# 10-power.net
KiCad netlist of a schematic drawn in Altium Designer
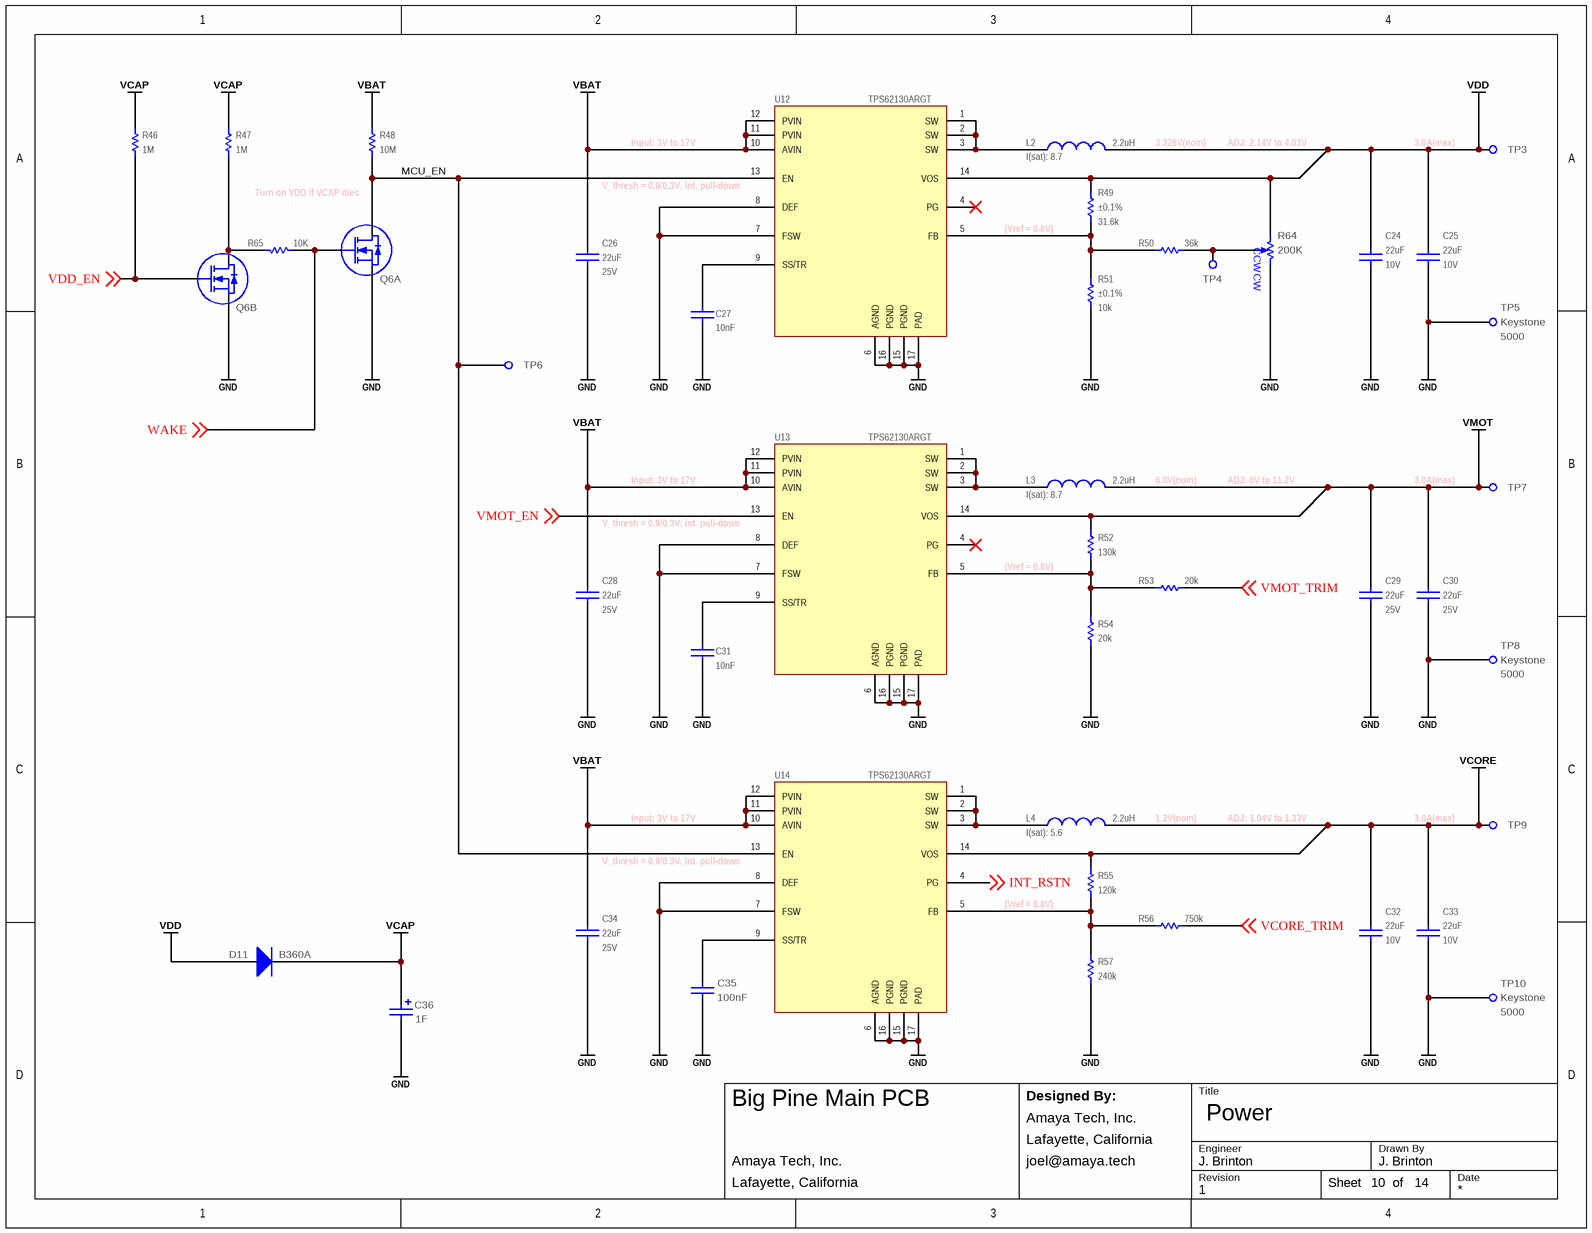
[diagram p0: 10-power.SchDoc]

(export (version "E")
  (design (tool "Eeschema 10.0.6"))
  (components
    (comp (ref "C24")
      (value "22uF")
      (footprint "CAPC200X125X145L45N")
      (description "Ceramic Capacitor 22uF ±20% 10V X7S 0805")
      (fields
        (field (name "MANUFACTURER") "TDK")
        (field (name "TOLERANCE") "±20%")
        (field (name "VOLTAGE") "10V")
      )
      (libsource (lib "") (part "CAP_1"))
    )
    (comp (ref "C25")
      (value "22uF")
      (footprint "CAPC200X125X145L45N")
      (description "Ceramic Capacitor 22uF ±20% 10V X7S 0805")
      (fields
        (field (name "MANUFACTURER") "TDK")
        (field (name "TOLERANCE") "±20%")
        (field (name "VOLTAGE") "10V")
      )
      (libsource (lib "") (part "CAP_1"))
    )
    (comp (ref "C26")
      (value "22uF")
      (footprint "CAPC320X250X270L50N")
      (description "Ceramic Capacitor 22uF ±10% 25V X7R 1210")
      (fields
        (field (name "MANUFACTURER") "Murata")
        (field (name "TOLERANCE") "±10%")
        (field (name "VOLTAGE") "25V")
      )
      (libsource (lib "generic") (part "CAP"))
    )
    (comp (ref "C27")
      (value "10nF")
      (footprint "CAPC100X50X55L25N")
      (description "Ceramic Capacitor 10nF ±10% 50V X7R 0402")
      (fields (field (name "MANUFACTURER") "Murata") (field (name "TOLERANCE") "±10%"))
      (libsource (lib "generic") (part "CAP"))
    )
    (comp (ref "C28")
      (value "22uF")
      (footprint "CAPC320X250X270L50N")
      (description "Ceramic Capacitor 22uF ±10% 25V X7R 1210")
      (fields
        (field (name "MANUFACTURER") "Murata")
        (field (name "TOLERANCE") "±10%")
        (field (name "VOLTAGE") "25V")
      )
      (libsource (lib "generic") (part "CAP"))
    )
    (comp (ref "C29")
      (value "22uF")
      (footprint "CAPC320X250X270L50N")
      (description "Ceramic Capacitor 22uF ±10% 25V X7R 1210")
      (fields
        (field (name "MANUFACTURER") "Murata")
        (field (name "TOLERANCE") "±10%")
        (field (name "VOLTAGE") "25V")
      )
      (libsource (lib "generic") (part "CAP"))
    )
    (comp (ref "C30")
      (value "22uF")
      (footprint "CAPC320X250X270L50N")
      (description "Ceramic Capacitor 22uF ±10% 25V X7R 1210")
      (fields
        (field (name "MANUFACTURER") "Murata")
        (field (name "TOLERANCE") "±10%")
        (field (name "VOLTAGE") "25V")
      )
      (libsource (lib "generic") (part "CAP"))
    )
    (comp (ref "C31")
      (value "10nF")
      (footprint "CAPC100X50X55L25N")
      (description "Ceramic Capacitor 10nF ±10% 50V X7R 0402")
      (fields (field (name "MANUFACTURER") "Murata") (field (name "TOLERANCE") "±10%"))
      (libsource (lib "generic") (part "CAP"))
    )
    (comp (ref "C32")
      (value "22uF")
      (footprint "CAPC200X125X145L45N")
      (description "Ceramic Capacitor 22uF ±20% 10V X7S 0805")
      (fields
        (field (name "MANUFACTURER") "TDK")
        (field (name "TOLERANCE") "±20%")
        (field (name "VOLTAGE") "10V")
      )
      (libsource (lib "") (part "CAP_1"))
    )
    (comp (ref "C33")
      (value "22uF")
      (footprint "CAPC200X125X145L45N")
      (description "Ceramic Capacitor 22uF ±20% 10V X7S 0805")
      (fields
        (field (name "MANUFACTURER") "TDK")
        (field (name "TOLERANCE") "±20%")
        (field (name "VOLTAGE") "10V")
      )
      (libsource (lib "") (part "CAP_1"))
    )
    (comp (ref "C34")
      (value "22uF")
      (footprint "CAPC320X250X270L50N")
      (description "Ceramic Capacitor 22uF ±10% 25V X7R 1210")
      (fields
        (field (name "MANUFACTURER") "Murata")
        (field (name "TOLERANCE") "±10%")
        (field (name "VOLTAGE") "25V")
      )
      (libsource (lib "generic") (part "CAP"))
    )
    (comp (ref "C35")
      (value "100nF")
      (footprint "CAPC200X125X145L45N")
      (description "Ceramic Capacitor 100nF ±10% 50V X7R 0805")
      (fields (field (name "MANUFACTURER") "Murata") (field (name "TOLERANCE") "±10%"))
      (libsource (lib "capacitors") (part "CAP"))
    )
    (comp (ref "C36")
      (value "1F")
      (footprint "DBJ-5R5D105T")
      (description "Super Capacitor 1F 5.5V Leaded")
      (fields (field (name "MANUFACTURER") "Elna") (field (name "VOLTAGE") "5.5V"))
      (libsource (lib "generic") (part "CAP_POL"))
    )
    (comp (ref "D11")
      (value "B360A")
      (footprint "SMA")
      (description "DIODE SCHOTTKY 60V 3A SMA")
      (fields (field (name "MANUFACTURER") "Diodes Inc"))
      (libsource (lib "diodes_inc") (part "D360A"))
    )
    (comp (ref "L2")
      (value "2.2uH")
      (footprint "coilcraft:XAL5030")
      (description "Shielded Power Inductor 2.2uH, 8.7A")
      (fields
        (field (name "MANUFACTURER") "Coilcraft")
        (field (name "I(SAT)") "8.7")
        (field (name "Comment") "XAL5030-332ME")
      )
      (libsource (lib "generic") (part "INDUCTOR"))
    )
    (comp (ref "L3")
      (value "2.2uH")
      (footprint "coilcraft:XAL5030")
      (description "Shielded Power Inductor 2.2uH, 8.7A")
      (fields
        (field (name "MANUFACTURER") "Coilcraft")
        (field (name "I(SAT)") "8.7")
        (field (name "Comment") "XAL5030-332ME")
      )
      (libsource (lib "generic") (part "INDUCTOR"))
    )
    (comp (ref "L4")
      (value "2.2uH")
      (footprint "coilcraft:XFL4020")
      (description "Shielded Power Inductor 2.2uH, 5.6A")
      (fields
        (field (name "MANUFACTURER") "Coilcraft")
        (field (name "I(SAT)") "5.6")
        (field (name "Comment") "XAL4020-222ME_")
      )
      (libsource (lib "generic") (part "INDUCTOR"))
    )
    (comp (ref "Q6")
      (value "2N7002DWQ-7-F")
      (footprint "SOT363")
      (description "Dual N-Channel Enhancement Mode MOSFET")
      (fields (field (name "MANUFACTURER") "Diodes, Inc."))
      (libsource (lib "") (part "2N7002DW-7-F_1"))
    )
    (comp (ref "R46")
      (value "1M")
      (footprint "RESC2012X70N")
      (description "Thick Film Resistor 1M ±1% 0805")
      (fields (field (name "MANUFACTURER") "Panasonic") (field (name "TOLERANCE") "±1%"))
      (libsource (lib "Graviton") (part "RES 0402"))
    )
    (comp (ref "R47")
      (value "1M")
      (footprint "RESC2012X70N")
      (description "Thick Film Resistor 1M ±1% 0805")
      (fields (field (name "MANUFACTURER") "Panasonic") (field (name "TOLERANCE") "±1%"))
      (libsource (lib "Graviton") (part "RES 0402"))
    )
    (comp (ref "R48")
      (value "10M")
      (footprint "RESC2012X70N")
      (description "Thick Film Resistor 10M ±1% 0805")
      (fields (field (name "MANUFACTURER") "Panasonic") (field (name "TOLERANCE") "±5%"))
      (libsource (lib "Graviton") (part "RES 0402"))
    )
    (comp (ref "R49")
      (value "31.6k")
      (footprint "RESC2012X70N")
      (description "Thin Film Resistor 31.6k ±0.1% 0.125W 100V 0805")
      (fields
        (field (name "TOLERANCE") "±0.1%")
        (field (name "MANUFACTURER") "Panasonic")
        (field (name "VOLTAGE") "100")
      )
      (libsource (lib "generic") (part "RES"))
    )
    (comp (ref "R50")
      (value "36k")
      (footprint "RESC2012X70N")
      (description "Thick Film Resistor 36k ±1% 0805")
      (fields (field (name "MANUFACTURER") "Panasonic") (field (name "TOLERANCE") "±1%"))
      (libsource (lib "Graviton") (part "RES 0402"))
    )
    (comp (ref "R51")
      (value "10k")
      (footprint "RESC2012X70N")
      (description "Thin Film Resistor 10k ±0.1% 0.125W 100V 0805")
      (fields
        (field (name "TOLERANCE") "±0.1%")
        (field (name "MANUFACTURER") "Panasonic")
        (field (name "VOLTAGE") "100")
      )
      (libsource (lib "generic") (part "RES"))
    )
    (comp (ref "R52")
      (value "130k")
      (footprint "RESC2012X70N")
      (description "Thick Film Resistor 130k ±1% 0805")
      (fields (field (name "MANUFACTURER") "Panasonic") (field (name "TOLERANCE") "±1%"))
      (libsource (lib "Graviton") (part "RES 0402"))
    )
    (comp (ref "R53")
      (value "20k")
      (footprint "RESC2012X70N")
      (description "Thick Film Resistor 20k ±1% 0805")
      (fields (field (name "MANUFACTURER") "Panasonic") (field (name "TOLERANCE") "±1%"))
      (libsource (lib "Graviton") (part "RES 0402"))
    )
    (comp (ref "R54")
      (value "20k")
      (footprint "RESC2012X70N")
      (description "Thick Film Resistor 20k ±1% 0805")
      (fields (field (name "MANUFACTURER") "Panasonic") (field (name "TOLERANCE") "±1%"))
      (libsource (lib "Graviton") (part "RES 0402"))
    )
    (comp (ref "R55")
      (value "120k")
      (footprint "RESC2012X70N")
      (description "Thick Film Resistor 120k ±1% 0805")
      (fields (field (name "MANUFACTURER") "Panasonic") (field (name "TOLERANCE") "±1%"))
      (libsource (lib "Graviton") (part "RES 0402"))
    )
    (comp (ref "R56")
      (value "750k")
      (footprint "RESC2012X70N")
      (description "Thick Film Resistor 750k ±1% 0805")
      (fields (field (name "MANUFACTURER") "Panasonic") (field (name "TOLERANCE") "±1%"))
      (libsource (lib "Graviton") (part "RES 0402"))
    )
    (comp (ref "R57")
      (value "240k")
      (footprint "RESC2012X70N")
      (description "Thick Film Resistor 240k ±1% 0805")
      (fields (field (name "MANUFACTURER") "Panasonic") (field (name "TOLERANCE") "±1%"))
      (libsource (lib "Graviton") (part "RES 0402"))
    )
    (comp (ref "R64")
      (value "200K")
      (footprint "PVG3A")
      (description "Trimmer 200K, sealed, cermet")
      (fields (field (name "MANUFACTURER") "Murata") (field (name "Comment") "PVG3A204C01R00"))
      (libsource (lib "bourns") (part "PVG3A204C01R00"))
    )
    (comp (ref "R65")
      (value "10K")
      (footprint "RESC2012X70N")
      (description "Thick Film Resistor 10k ±1% 0805")
      (fields (field (name "MANUFACTURER") "Panasonic") (field (name "TOLERANCE") "±1%"))
      (libsource (lib "Graviton") (part "RES 0402"))
    )
    (comp (ref "TP3")
      (value "TEST_POINT_SMD_50")
      (footprint "generic:TEST_POINT_SMD_50")
      (description "Test Point SMD")
      (libsource (lib "generic") (part "TEST_POINT_SMD_50"))
    )
    (comp (ref "TP4")
      (value "TEST_POINT_SMD_50")
      (footprint "generic:TEST_POINT_SMD_50")
      (description "Test Point SMD")
      (libsource (lib "generic") (part "TEST_POINT_SMD_50"))
    )
    (comp (ref "TP5")
      (value "5000")
      (footprint "TEST_POINT")
      (description "Thruhole Miniature Test Point")
      (fields (field (name "MANUFACTURER") "Keystone"))
      (libsource (lib "generic") (part "TEST_POINT"))
    )
    (comp (ref "TP6")
      (value "TEST_POINT_SMD_50")
      (footprint "generic:TEST_POINT_SMD_50")
      (description "Test Point SMD")
      (libsource (lib "generic") (part "TEST_POINT_SMD_50"))
    )
    (comp (ref "TP7")
      (value "TEST_POINT_SMD_50")
      (footprint "generic:TEST_POINT_SMD_50")
      (description "Test Point SMD")
      (libsource (lib "generic") (part "TEST_POINT_SMD_50"))
    )
    (comp (ref "TP8")
      (value "5000")
      (footprint "TEST_POINT")
      (description "Thruhole Miniature Test Point")
      (fields (field (name "MANUFACTURER") "Keystone"))
      (libsource (lib "generic") (part "TEST_POINT"))
    )
    (comp (ref "TP9")
      (value "TEST_POINT_SMD_50")
      (footprint "generic:TEST_POINT_SMD_50")
      (description "Test Point SMD")
      (libsource (lib "generic") (part "TEST_POINT_SMD_50"))
    )
    (comp (ref "TP10")
      (value "5000")
      (footprint "TEST_POINT")
      (description "Thruhole Miniature Test Point")
      (fields (field (name "MANUFACTURER") "Keystone"))
      (libsource (lib "generic") (part "TEST_POINT"))
    )
    (comp (ref "U12")
      (value "TPS62130ARGT")
      (footprint "S-PQFP-8N")
      (description "3-17V 3A Step-Down Converter VQFN")
      (fields (field (name "MANUFACTURER") "Texas Instruments"))
      (libsource (lib "ti") (part "TPS62130RGT"))
    )
    (comp (ref "U13")
      (value "TPS62130ARGT")
      (footprint "S-PQFP-8N")
      (description "3-17V 3A Step-Down Converter VQFN")
      (fields (field (name "MANUFACTURER") "Texas Instruments"))
      (libsource (lib "ti") (part "TPS62130RGT"))
    )
    (comp (ref "U14")
      (value "TPS62130ARGT")
      (footprint "S-PQFP-8N")
      (description "3-17V 3A Step-Down Converter VQFN")
      (fields (field (name "MANUFACTURER") "Texas Instruments"))
      (libsource (lib "ti") (part "TPS62130RGT"))
    )
  )
  (nets
    (net (code "1") (name "/MCU_EN") (class "Default")
      (node (ref "Q6") (pin "3") (pinfunction "D1_3") (pintype "passive"))
      (node (ref "R48") (pin "1") (pinfunction "1_1") (pintype "passive"))
      (node (ref "TP6") (pin "1") (pinfunction "1_1") (pintype "passive"))
      (node (ref "U12") (pin "13") (pinfunction "EN_13") (pintype "passive"))
      (node (ref "U14") (pin "13") (pinfunction "EN_13") (pintype "passive"))
    )
    (net (code "2") (name "GND") (class "Default")
      (node (ref "C24") (pin "1") (pinfunction "1_1") (pintype "passive"))
      (node (ref "C25") (pin "1") (pinfunction "1_1") (pintype "passive"))
      (node (ref "C26") (pin "1") (pinfunction "1_1") (pintype "passive"))
      (node (ref "C27") (pin "2") (pinfunction "2_2") (pintype "passive"))
      (node (ref "C28") (pin "1") (pinfunction "1_1") (pintype "passive"))
      (node (ref "C29") (pin "1") (pinfunction "1_1") (pintype "passive"))
      (node (ref "C30") (pin "1") (pinfunction "1_1") (pintype "passive"))
      (node (ref "C31") (pin "2") (pinfunction "2_2") (pintype "passive"))
      (node (ref "C32") (pin "1") (pinfunction "1_1") (pintype "passive"))
      (node (ref "C33") (pin "1") (pinfunction "1_1") (pintype "passive"))
      (node (ref "C34") (pin "1") (pinfunction "1_1") (pintype "passive"))
      (node (ref "C35") (pin "2") (pinfunction "2_2") (pintype "passive"))
      (node (ref "C36") (pin "2") (pinfunction "2_2") (pintype "passive"))
      (node (ref "Q6") (pin "1") (pinfunction "S2_1") (pintype "passive"))
      (node (ref "Q6") (pin "4") (pinfunction "S1_4") (pintype "passive"))
      (node (ref "R51") (pin "1") (pinfunction "1_1") (pintype "passive"))
      (node (ref "R54") (pin "1") (pinfunction "1_1") (pintype "passive"))
      (node (ref "R57") (pin "1") (pinfunction "1_1") (pintype "passive"))
      (node (ref "R64") (pin "3") (pinfunction "CW_3") (pintype "passive"))
      (node (ref "TP10") (pin "1") (pinfunction "1_1") (pintype "passive"))
      (node (ref "TP5") (pin "1") (pinfunction "1_1") (pintype "passive"))
      (node (ref "TP8") (pin "1") (pinfunction "1_1") (pintype "passive"))
      (node (ref "U12") (pin "15") (pinfunction "PGND_15") (pintype "passive"))
      (node (ref "U12") (pin "16") (pinfunction "PGND_16") (pintype "passive"))
      (node (ref "U12") (pin "17") (pinfunction "PAD_17") (pintype "passive"))
      (node (ref "U12") (pin "6") (pinfunction "AGND_6") (pintype "passive"))
      (node (ref "U12") (pin "7") (pinfunction "FSW_7") (pintype "passive"))
      (node (ref "U12") (pin "8") (pinfunction "DEF_8") (pintype "passive"))
      (node (ref "U13") (pin "15") (pinfunction "PGND_15") (pintype "passive"))
      (node (ref "U13") (pin "16") (pinfunction "PGND_16") (pintype "passive"))
      (node (ref "U13") (pin "17") (pinfunction "PAD_17") (pintype "passive"))
      (node (ref "U13") (pin "6") (pinfunction "AGND_6") (pintype "passive"))
      (node (ref "U13") (pin "7") (pinfunction "FSW_7") (pintype "passive"))
      (node (ref "U13") (pin "8") (pinfunction "DEF_8") (pintype "passive"))
      (node (ref "U14") (pin "15") (pinfunction "PGND_15") (pintype "passive"))
      (node (ref "U14") (pin "16") (pinfunction "PGND_16") (pintype "passive"))
      (node (ref "U14") (pin "17") (pinfunction "PAD_17") (pintype "passive"))
      (node (ref "U14") (pin "6") (pinfunction "AGND_6") (pintype "passive"))
      (node (ref "U14") (pin "7") (pinfunction "FSW_7") (pintype "passive"))
      (node (ref "U14") (pin "8") (pinfunction "DEF_8") (pintype "passive"))
    )
    (net (code "3") (name "INT_RSTN") (class "Default")
      (node (ref "U14") (pin "4") (pinfunction "PG_4") (pintype "passive"))
    )
    (net (code "4") (name "Net-(L2-Pad1)") (class "Default")
      (node (ref "L2") (pin "1") (pinfunction "1_1") (pintype "passive"))
      (node (ref "U12") (pin "1") (pinfunction "SW_1") (pintype "passive"))
      (node (ref "U12") (pin "2") (pinfunction "SW_2") (pintype "passive"))
      (node (ref "U12") (pin "3") (pinfunction "SW_3") (pintype "passive"))
    )
    (net (code "5") (name "Net-(L3-Pad1)") (class "Default")
      (node (ref "L3") (pin "1") (pinfunction "1_1") (pintype "passive"))
      (node (ref "U13") (pin "1") (pinfunction "SW_1") (pintype "passive"))
      (node (ref "U13") (pin "2") (pinfunction "SW_2") (pintype "passive"))
      (node (ref "U13") (pin "3") (pinfunction "SW_3") (pintype "passive"))
    )
    (net (code "6") (name "Net-(L4-Pad1)") (class "Default")
      (node (ref "L4") (pin "1") (pinfunction "1_1") (pintype "passive"))
      (node (ref "U14") (pin "1") (pinfunction "SW_1") (pintype "passive"))
      (node (ref "U14") (pin "2") (pinfunction "SW_2") (pintype "passive"))
      (node (ref "U14") (pin "3") (pinfunction "SW_3") (pintype "passive"))
    )
    (net (code "7") (name "Net-(Q6B-D2)") (class "Default")
      (node (ref "Q6") (pin "6") (pinfunction "D2_6") (pintype "passive"))
      (node (ref "R47") (pin "1") (pinfunction "1_1") (pintype "passive"))
      (node (ref "R65") (pin "2") (pinfunction "2_2") (pintype "passive"))
    )
    (net (code "8") (name "Net-(R64-CT)") (class "Default")
      (node (ref "R50") (pin "1") (pinfunction "1_1") (pintype "passive"))
      (node (ref "R64") (pin "2") (pinfunction "CT_2") (pintype "passive"))
      (node (ref "TP4") (pin "1") (pinfunction "1_1") (pintype "passive"))
    )
    (net (code "9") (name "Net-(U12-FB)") (class "Default")
      (node (ref "R49") (pin "1") (pinfunction "1_1") (pintype "passive"))
      (node (ref "R50") (pin "2") (pinfunction "2_2") (pintype "passive"))
      (node (ref "R51") (pin "2") (pinfunction "2_2") (pintype "passive"))
      (node (ref "U12") (pin "5") (pinfunction "FB_5") (pintype "passive"))
    )
    (net (code "10") (name "Net-(U12-SS{slash}TR)") (class "Default")
      (node (ref "C27") (pin "1") (pinfunction "1_1") (pintype "passive"))
      (node (ref "U12") (pin "9") (pinfunction "SS/TR_9") (pintype "passive"))
    )
    (net (code "11") (name "Net-(U13-FB)") (class "Default")
      (node (ref "R52") (pin "1") (pinfunction "1_1") (pintype "passive"))
      (node (ref "R53") (pin "2") (pinfunction "2_2") (pintype "passive"))
      (node (ref "R54") (pin "2") (pinfunction "2_2") (pintype "passive"))
      (node (ref "U13") (pin "5") (pinfunction "FB_5") (pintype "passive"))
    )
    (net (code "12") (name "Net-(U13-SS{slash}TR)") (class "Default")
      (node (ref "C31") (pin "1") (pinfunction "1_1") (pintype "passive"))
      (node (ref "U13") (pin "9") (pinfunction "SS/TR_9") (pintype "passive"))
    )
    (net (code "13") (name "Net-(U14-FB)") (class "Default")
      (node (ref "R55") (pin "1") (pinfunction "1_1") (pintype "passive"))
      (node (ref "R56") (pin "2") (pinfunction "2_2") (pintype "passive"))
      (node (ref "R57") (pin "2") (pinfunction "2_2") (pintype "passive"))
      (node (ref "U14") (pin "5") (pinfunction "FB_5") (pintype "passive"))
    )
    (net (code "14") (name "Net-(U14-SS{slash}TR)") (class "Default")
      (node (ref "C35") (pin "1") (pinfunction "1_1") (pintype "passive"))
      (node (ref "U14") (pin "9") (pinfunction "SS/TR_9") (pintype "passive"))
    )
    (net (code "15") (name "VBAT") (class "Default")
      (node (ref "C26") (pin "2") (pinfunction "2_2") (pintype "passive"))
      (node (ref "C28") (pin "2") (pinfunction "2_2") (pintype "passive"))
      (node (ref "C34") (pin "2") (pinfunction "2_2") (pintype "passive"))
      (node (ref "R48") (pin "2") (pinfunction "2_2") (pintype "passive"))
      (node (ref "U12") (pin "10") (pinfunction "AVIN_10") (pintype "passive"))
      (node (ref "U12") (pin "11") (pinfunction "PVIN_11") (pintype "passive"))
      (node (ref "U12") (pin "12") (pinfunction "PVIN_12") (pintype "passive"))
      (node (ref "U13") (pin "10") (pinfunction "AVIN_10") (pintype "passive"))
      (node (ref "U13") (pin "11") (pinfunction "PVIN_11") (pintype "passive"))
      (node (ref "U13") (pin "12") (pinfunction "PVIN_12") (pintype "passive"))
      (node (ref "U14") (pin "10") (pinfunction "AVIN_10") (pintype "passive"))
      (node (ref "U14") (pin "11") (pinfunction "PVIN_11") (pintype "passive"))
      (node (ref "U14") (pin "12") (pinfunction "PVIN_12") (pintype "passive"))
    )
    (net (code "16") (name "VCAP") (class "Default")
      (node (ref "C36") (pin "1") (pinfunction "1_1") (pintype "passive"))
      (node (ref "D11") (pin "2") (pinfunction "K_2") (pintype "passive"))
      (node (ref "R46") (pin "2") (pinfunction "2_2") (pintype "passive"))
      (node (ref "R47") (pin "2") (pinfunction "2_2") (pintype "passive"))
    )
    (net (code "17") (name "VCORE") (class "Default")
      (node (ref "C32") (pin "2") (pinfunction "2_2") (pintype "passive"))
      (node (ref "C33") (pin "2") (pinfunction "2_2") (pintype "passive"))
      (node (ref "L4") (pin "2") (pinfunction "2_2") (pintype "passive"))
      (node (ref "R55") (pin "2") (pinfunction "2_2") (pintype "passive"))
      (node (ref "TP9") (pin "1") (pinfunction "1_1") (pintype "passive"))
      (node (ref "U14") (pin "14") (pinfunction "VOS_14") (pintype "passive"))
    )
    (net (code "18") (name "VCORE_TRIM") (class "Default")
      (node (ref "R56") (pin "1") (pinfunction "1_1") (pintype "passive"))
    )
    (net (code "19") (name "VDD") (class "Default")
      (node (ref "C24") (pin "2") (pinfunction "2_2") (pintype "passive"))
      (node (ref "C25") (pin "2") (pinfunction "2_2") (pintype "passive"))
      (node (ref "D11") (pin "1") (pinfunction "A_1") (pintype "power_in"))
      (node (ref "L2") (pin "2") (pinfunction "2_2") (pintype "passive"))
      (node (ref "R49") (pin "2") (pinfunction "2_2") (pintype "passive"))
      (node (ref "R64") (pin "1") (pinfunction "CCW_1") (pintype "passive"))
      (node (ref "TP3") (pin "1") (pinfunction "1_1") (pintype "passive"))
      (node (ref "U12") (pin "14") (pinfunction "VOS_14") (pintype "passive"))
    )
    (net (code "20") (name "VDD_EN") (class "Default")
      (node (ref "Q6") (pin "2") (pinfunction "G2_2") (pintype "passive"))
      (node (ref "R46") (pin "1") (pinfunction "1_1") (pintype "passive"))
    )
    (net (code "21") (name "VMOT") (class "Default")
      (node (ref "C29") (pin "2") (pinfunction "2_2") (pintype "passive"))
      (node (ref "C30") (pin "2") (pinfunction "2_2") (pintype "passive"))
      (node (ref "L3") (pin "2") (pinfunction "2_2") (pintype "passive"))
      (node (ref "R52") (pin "2") (pinfunction "2_2") (pintype "passive"))
      (node (ref "TP7") (pin "1") (pinfunction "1_1") (pintype "passive"))
      (node (ref "U13") (pin "14") (pinfunction "VOS_14") (pintype "passive"))
    )
    (net (code "22") (name "VMOT_EN") (class "Default")
      (node (ref "U13") (pin "13") (pinfunction "EN_13") (pintype "passive"))
    )
    (net (code "23") (name "VMOT_TRIM") (class "Default")
      (node (ref "R53") (pin "1") (pinfunction "1_1") (pintype "passive"))
    )
    (net (code "24") (name "WAKE") (class "Default")
      (node (ref "Q6") (pin "5") (pinfunction "G1_5") (pintype "passive"))
      (node (ref "R65") (pin "1") (pinfunction "1_1") (pintype "passive"))
    )
    (net (code "25") (name "unconnected-(U12-PG-Pad4)") (class "Default")
      (node (ref "U12") (pin "4") (pinfunction "PG_4") (pintype "passive+no_connect"))
    )
    (net (code "26") (name "unconnected-(U13-PG-Pad4)") (class "Default")
      (node (ref "U13") (pin "4") (pinfunction "PG_4") (pintype "passive+no_connect"))
    )
  )
)
